# Circlez8a_v2.net
KiCad netlist of a schematic drawn in EAGLE
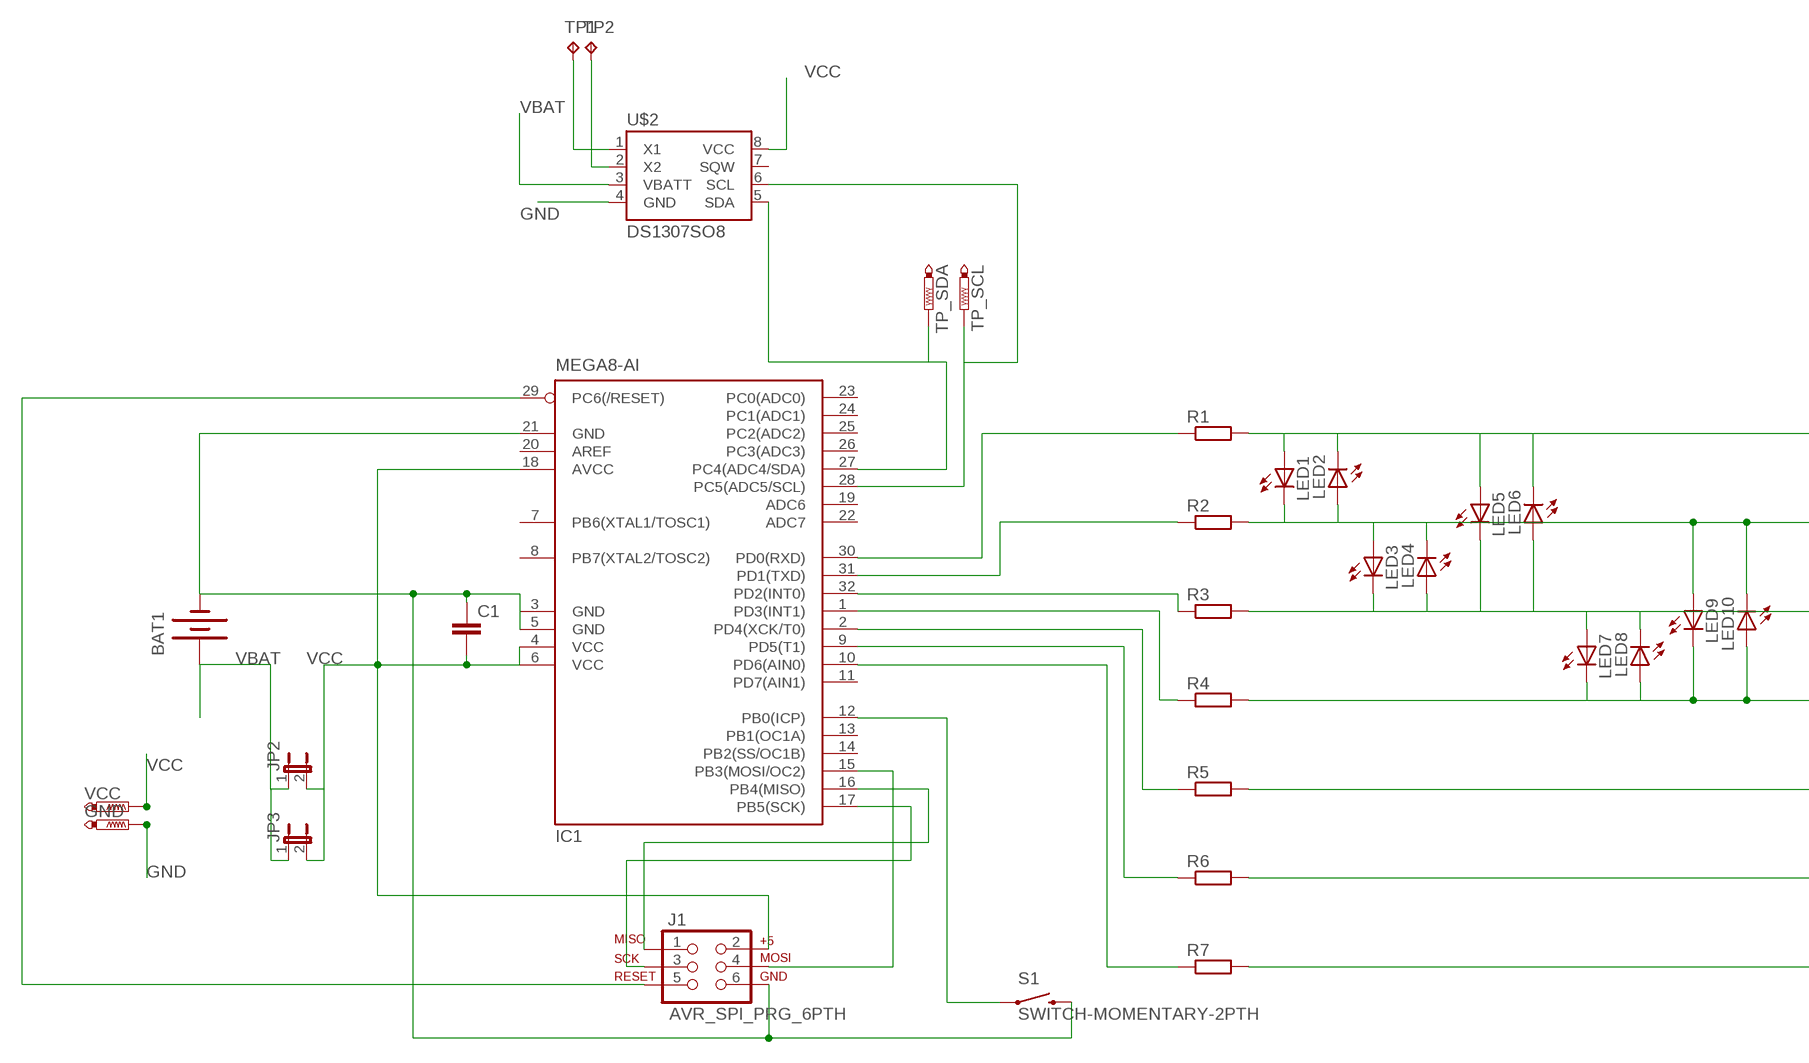
[diagram p0: schematic, sheet 1, part 1 of 2]
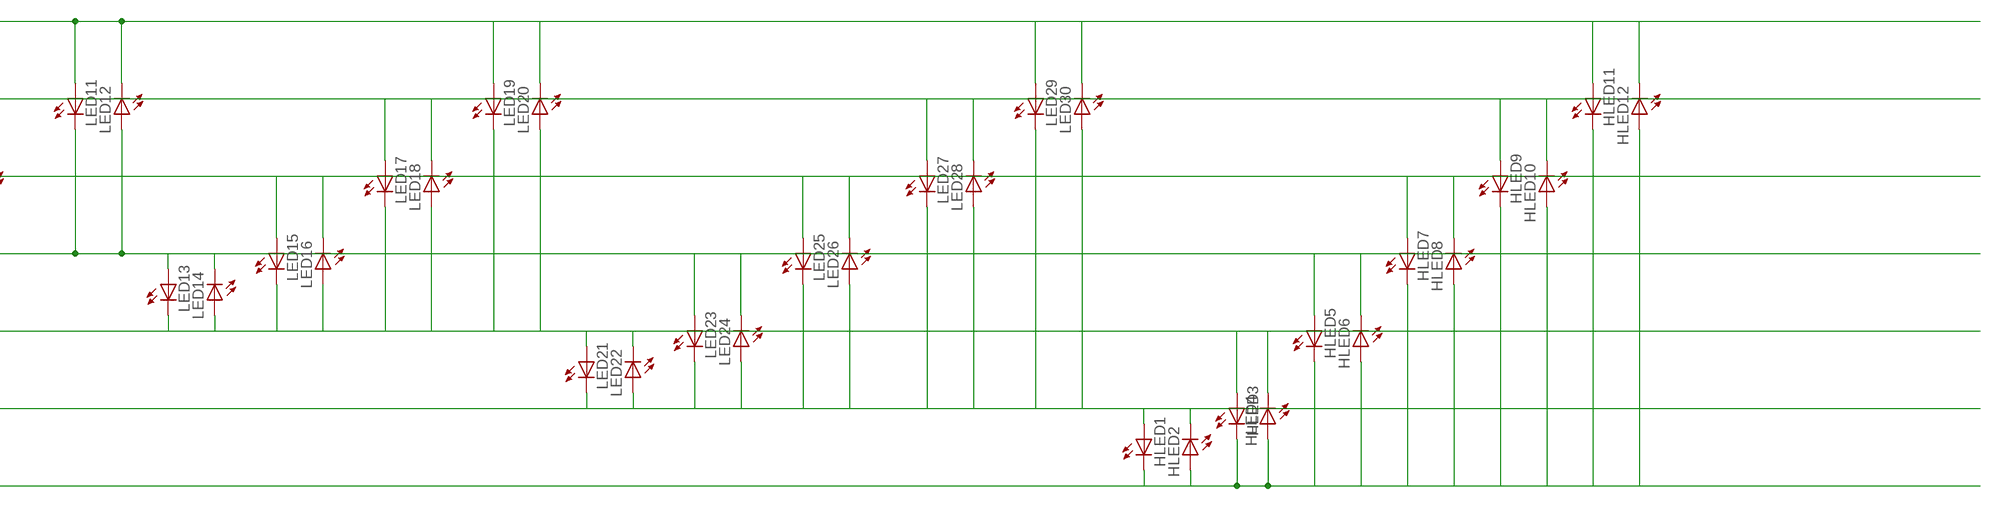
[diagram p1: schematic, sheet 1, part 2 of 2]

(export (version "E")
  (design (tool "Eeschema 10.0.6"))
  (components
    (comp (ref "BAT1")
      (value "BATTERY20PTH")
      (footprint "eagle-import:BATTCOM_20MM_PTH")
      (libsource (lib "eagle-import") (part "BATTERY20PTH"))
    )
    (comp (ref "C1")
      (value "C-EU025-024X044")
      (footprint "eagle-import:C025-024X044")
      (libsource (lib "eagle-import") (part "C-EU025-024X044"))
    )
    (comp (ref "GND")
      (value "PTR1TP15SQ")
      (footprint "eagle-import:TP15SQ")
      (libsource (lib "eagle-import") (part "PTR1TP15SQ"))
    )
    (comp (ref "HLED1")
      (value "LEDCHIP-LED0603")
      (footprint "eagle-import:CHIP-LED0603")
      (libsource (lib "eagle-import") (part "LEDCHIP-LED0603"))
    )
    (comp (ref "HLED2")
      (value "LEDCHIP-LED0603")
      (footprint "eagle-import:CHIP-LED0603")
      (libsource (lib "eagle-import") (part "LEDCHIP-LED0603"))
    )
    (comp (ref "HLED3")
      (value "LEDCHIP-LED0603")
      (footprint "eagle-import:CHIP-LED0603")
      (libsource (lib "eagle-import") (part "LEDCHIP-LED0603"))
    )
    (comp (ref "HLED4")
      (value "LEDCHIP-LED0603")
      (footprint "eagle-import:CHIP-LED0603")
      (libsource (lib "eagle-import") (part "LEDCHIP-LED0603"))
    )
    (comp (ref "HLED5")
      (value "LEDCHIP-LED0603")
      (footprint "eagle-import:CHIP-LED0603")
      (libsource (lib "eagle-import") (part "LEDCHIP-LED0603"))
    )
    (comp (ref "HLED6")
      (value "LEDCHIP-LED0603")
      (footprint "eagle-import:CHIP-LED0603")
      (libsource (lib "eagle-import") (part "LEDCHIP-LED0603"))
    )
    (comp (ref "HLED7")
      (value "LEDCHIP-LED0603")
      (footprint "eagle-import:CHIP-LED0603")
      (libsource (lib "eagle-import") (part "LEDCHIP-LED0603"))
    )
    (comp (ref "HLED8")
      (value "LEDCHIP-LED0603")
      (footprint "eagle-import:CHIP-LED0603")
      (libsource (lib "eagle-import") (part "LEDCHIP-LED0603"))
    )
    (comp (ref "HLED9")
      (value "LEDCHIP-LED0603")
      (footprint "eagle-import:CHIP-LED0603")
      (libsource (lib "eagle-import") (part "LEDCHIP-LED0603"))
    )
    (comp (ref "HLED10")
      (value "LEDCHIP-LED0603")
      (footprint "eagle-import:CHIP-LED0603")
      (libsource (lib "eagle-import") (part "LEDCHIP-LED0603"))
    )
    (comp (ref "HLED11")
      (value "LEDCHIP-LED0603")
      (footprint "eagle-import:CHIP-LED0603")
      (libsource (lib "eagle-import") (part "LEDCHIP-LED0603"))
    )
    (comp (ref "HLED12")
      (value "LEDCHIP-LED0603")
      (footprint "eagle-import:CHIP-LED0603")
      (libsource (lib "eagle-import") (part "LEDCHIP-LED0603"))
    )
    (comp (ref "IC1")
      (value "MEGA8-AI")
      (footprint "eagle-import:TQFP32-08")
      (fields (field (name "MPN") "ATMEGA8-16AU"))
      (libsource (lib "eagle-import") (part "MEGA8-AI"))
    )
    (comp (ref "J1")
      (value "AVR_SPI_PRG_6PTH")
      (footprint "eagle-import:2X3")
      (libsource (lib "eagle-import") (part "AVR_SPI_PRG_6PTH"))
    )
    (comp (ref "JP2")
      (value "JUMPER-2SMD-NO")
      (footprint "eagle-import:SJ_2S-NO")
      (libsource (lib "eagle-import") (part "JUMPER-2SMD-NO"))
    )
    (comp (ref "JP3")
      (value "JUMPER-2PTH")
      (footprint "eagle-import:1X02")
      (libsource (lib "eagle-import") (part "JUMPER-2PTH"))
    )
    (comp (ref "LED1")
      (value "LEDCHIPLED_0603")
      (footprint "eagle-import:CHIPLED_0603")
      (libsource (lib "eagle-import") (part "LEDCHIPLED_0603"))
    )
    (comp (ref "LED2")
      (value "LEDCHIPLED_0603")
      (footprint "eagle-import:CHIPLED_0603")
      (libsource (lib "eagle-import") (part "LEDCHIPLED_0603"))
    )
    (comp (ref "LED3")
      (value "LEDCHIPLED_0603")
      (footprint "eagle-import:CHIPLED_0603")
      (libsource (lib "eagle-import") (part "LEDCHIPLED_0603"))
    )
    (comp (ref "LED4")
      (value "LEDCHIPLED_0603")
      (footprint "eagle-import:CHIPLED_0603")
      (libsource (lib "eagle-import") (part "LEDCHIPLED_0603"))
    )
    (comp (ref "LED5")
      (value "LEDCHIPLED_0603")
      (footprint "eagle-import:CHIPLED_0603")
      (libsource (lib "eagle-import") (part "LEDCHIPLED_0603"))
    )
    (comp (ref "LED6")
      (value "LEDCHIPLED_0603")
      (footprint "eagle-import:CHIPLED_0603")
      (libsource (lib "eagle-import") (part "LEDCHIPLED_0603"))
    )
    (comp (ref "LED7")
      (value "LEDCHIPLED_0603")
      (footprint "eagle-import:CHIPLED_0603")
      (libsource (lib "eagle-import") (part "LEDCHIPLED_0603"))
    )
    (comp (ref "LED8")
      (value "LEDCHIPLED_0603")
      (footprint "eagle-import:CHIPLED_0603")
      (libsource (lib "eagle-import") (part "LEDCHIPLED_0603"))
    )
    (comp (ref "LED9")
      (value "LEDCHIPLED_0603")
      (footprint "eagle-import:CHIPLED_0603")
      (libsource (lib "eagle-import") (part "LEDCHIPLED_0603"))
    )
    (comp (ref "LED10")
      (value "LEDCHIPLED_0603")
      (footprint "eagle-import:CHIPLED_0603")
      (libsource (lib "eagle-import") (part "LEDCHIPLED_0603"))
    )
    (comp (ref "LED11")
      (value "LEDCHIPLED_0603")
      (footprint "eagle-import:CHIPLED_0603")
      (libsource (lib "eagle-import") (part "LEDCHIPLED_0603"))
    )
    (comp (ref "LED12")
      (value "LEDCHIPLED_0603")
      (footprint "eagle-import:CHIPLED_0603")
      (libsource (lib "eagle-import") (part "LEDCHIPLED_0603"))
    )
    (comp (ref "LED13")
      (value "LEDCHIPLED_0603")
      (footprint "eagle-import:CHIPLED_0603")
      (libsource (lib "eagle-import") (part "LEDCHIPLED_0603"))
    )
    (comp (ref "LED14")
      (value "LEDCHIPLED_0603")
      (footprint "eagle-import:CHIPLED_0603")
      (libsource (lib "eagle-import") (part "LEDCHIPLED_0603"))
    )
    (comp (ref "LED15")
      (value "LEDCHIPLED_0603")
      (footprint "eagle-import:CHIPLED_0603")
      (libsource (lib "eagle-import") (part "LEDCHIPLED_0603"))
    )
    (comp (ref "LED16")
      (value "LEDCHIPLED_0603")
      (footprint "eagle-import:CHIPLED_0603")
      (libsource (lib "eagle-import") (part "LEDCHIPLED_0603"))
    )
    (comp (ref "LED17")
      (value "LEDCHIPLED_0603")
      (footprint "eagle-import:CHIPLED_0603")
      (libsource (lib "eagle-import") (part "LEDCHIPLED_0603"))
    )
    (comp (ref "LED18")
      (value "LEDCHIPLED_0603")
      (footprint "eagle-import:CHIPLED_0603")
      (libsource (lib "eagle-import") (part "LEDCHIPLED_0603"))
    )
    (comp (ref "LED19")
      (value "LEDCHIPLED_0603")
      (footprint "eagle-import:CHIPLED_0603")
      (libsource (lib "eagle-import") (part "LEDCHIPLED_0603"))
    )
    (comp (ref "LED20")
      (value "LEDCHIPLED_0603")
      (footprint "eagle-import:CHIPLED_0603")
      (libsource (lib "eagle-import") (part "LEDCHIPLED_0603"))
    )
    (comp (ref "LED21")
      (value "LEDCHIPLED_0603")
      (footprint "eagle-import:CHIPLED_0603")
      (libsource (lib "eagle-import") (part "LEDCHIPLED_0603"))
    )
    (comp (ref "LED22")
      (value "LEDCHIPLED_0603")
      (footprint "eagle-import:CHIPLED_0603")
      (libsource (lib "eagle-import") (part "LEDCHIPLED_0603"))
    )
    (comp (ref "LED23")
      (value "LEDCHIPLED_0603")
      (footprint "eagle-import:CHIPLED_0603")
      (libsource (lib "eagle-import") (part "LEDCHIPLED_0603"))
    )
    (comp (ref "LED24")
      (value "LEDCHIPLED_0603")
      (footprint "eagle-import:CHIPLED_0603")
      (libsource (lib "eagle-import") (part "LEDCHIPLED_0603"))
    )
    (comp (ref "LED25")
      (value "LEDCHIPLED_0603")
      (footprint "eagle-import:CHIPLED_0603")
      (libsource (lib "eagle-import") (part "LEDCHIPLED_0603"))
    )
    (comp (ref "LED26")
      (value "LEDCHIPLED_0603")
      (footprint "eagle-import:CHIPLED_0603")
      (libsource (lib "eagle-import") (part "LEDCHIPLED_0603"))
    )
    (comp (ref "LED27")
      (value "LEDCHIPLED_0603")
      (footprint "eagle-import:CHIPLED_0603")
      (libsource (lib "eagle-import") (part "LEDCHIPLED_0603"))
    )
    (comp (ref "LED28")
      (value "LEDCHIPLED_0603")
      (footprint "eagle-import:CHIPLED_0603")
      (libsource (lib "eagle-import") (part "LEDCHIPLED_0603"))
    )
    (comp (ref "LED29")
      (value "LEDCHIPLED_0603")
      (footprint "eagle-import:CHIPLED_0603")
      (libsource (lib "eagle-import") (part "LEDCHIPLED_0603"))
    )
    (comp (ref "LED30")
      (value "LEDCHIPLED_0603")
      (footprint "eagle-import:CHIPLED_0603")
      (libsource (lib "eagle-import") (part "LEDCHIPLED_0603"))
    )
    (comp (ref "R1")
      (value "R-EU_R1206")
      (footprint "eagle-import:R1206")
      (libsource (lib "eagle-import") (part "R-EU_R1206"))
    )
    (comp (ref "R2")
      (value "R-EU_R1206")
      (footprint "eagle-import:R1206")
      (libsource (lib "eagle-import") (part "R-EU_R1206"))
    )
    (comp (ref "R3")
      (value "R-EU_R1206")
      (footprint "eagle-import:R1206")
      (libsource (lib "eagle-import") (part "R-EU_R1206"))
    )
    (comp (ref "R4")
      (value "R-EU_R1206")
      (footprint "eagle-import:R1206")
      (libsource (lib "eagle-import") (part "R-EU_R1206"))
    )
    (comp (ref "R5")
      (value "R-EU_R1206")
      (footprint "eagle-import:R1206")
      (libsource (lib "eagle-import") (part "R-EU_R1206"))
    )
    (comp (ref "R6")
      (value "R-EU_R1206")
      (footprint "eagle-import:R1206")
      (libsource (lib "eagle-import") (part "R-EU_R1206"))
    )
    (comp (ref "R7")
      (value "R-EU_R1206")
      (footprint "eagle-import:R1206")
      (libsource (lib "eagle-import") (part "R-EU_R1206"))
    )
    (comp (ref "S1")
      (value "SWITCH-MOMENTARY-2PTH")
      (footprint "eagle-import:TACTILE-PTH")
      (libsource (lib "eagle-import") (part "SWITCH-MOMENTARY-2PTH"))
    )
    (comp (ref "TP1")
      (value "TPTP13SQ")
      (footprint "eagle-import:TP13SQ")
      (libsource (lib "eagle-import") (part "TPTP13SQ"))
    )
    (comp (ref "TP2")
      (value "TPTP13SQ")
      (footprint "eagle-import:TP13SQ")
      (libsource (lib "eagle-import") (part "TPTP13SQ"))
    )
    (comp (ref "TP_SCL")
      (value "PTR1TP09SQ")
      (footprint "eagle-import:TP09SQ")
      (libsource (lib "eagle-import") (part "PTR1TP09SQ"))
    )
    (comp (ref "TP_SDA")
      (value "PTR1TP09SQ")
      (footprint "eagle-import:TP09SQ")
      (libsource (lib "eagle-import") (part "PTR1TP09SQ"))
    )
    (comp (ref "U$2")
      (value "DS1307SO8")
      (footprint "eagle-import:SO08")
      (libsource (lib "eagle-import") (part "DS1307SO8"))
    )
    (comp (ref "VCC")
      (value "PTR1TP15SQ")
      (footprint "eagle-import:TP15SQ")
      (libsource (lib "eagle-import") (part "PTR1TP15SQ"))
    )
  )
  (nets
    (net (code "1") (name "/GND") (class "Default")
      (node (ref "BAT1") (pin "2") (pinfunction "-_2") (pintype "power_in"))
      (node (ref "C1") (pin "1") (pinfunction "1_1") (pintype "passive"))
      (node (ref "GND") (pin "TP") (pinfunction "TP_TP") (pintype "input"))
      (node (ref "IC1") (pin "21") (pinfunction "GND_21") (pintype "power_in"))
      (node (ref "IC1") (pin "3") (pinfunction "GND_3") (pintype "power_in"))
      (node (ref "IC1") (pin "5") (pinfunction "GND_5") (pintype "power_in"))
      (node (ref "J1") (pin "6") (pinfunction "6_6") (pintype "passive"))
      (node (ref "S1") (pin "3") (pinfunction "2_3") (pintype "passive"))
      (node (ref "U$2") (pin "4") (pinfunction "GND_4") (pintype "bidirectional"))
    )
    (net (code "2") (name "/VBAT") (class "Default")
      (node (ref "BAT1") (pin "1") (pinfunction "+_1") (pintype "power_in"))
      (node (ref "JP2") (pin "1") (pinfunction "1_1") (pintype "passive"))
      (node (ref "JP3") (pin "1") (pinfunction "1_1") (pintype "passive"))
      (node (ref "U$2") (pin "3") (pinfunction "VBATT_3") (pintype "bidirectional"))
    )
    (net (code "3") (name "/VCC") (class "Default")
      (node (ref "C1") (pin "2") (pinfunction "2_2") (pintype "passive"))
      (node (ref "IC1") (pin "18") (pinfunction "AVCC_18") (pintype "power_in"))
      (node (ref "IC1") (pin "4") (pinfunction "VCC_4") (pintype "power_in"))
      (node (ref "IC1") (pin "6") (pinfunction "VCC_6") (pintype "power_in"))
      (node (ref "J1") (pin "2") (pinfunction "2_2") (pintype "passive"))
      (node (ref "JP2") (pin "2") (pinfunction "2_2") (pintype "passive"))
      (node (ref "JP3") (pin "2") (pinfunction "2_2") (pintype "passive"))
      (node (ref "U$2") (pin "8") (pinfunction "VCC_8") (pintype "bidirectional"))
      (node (ref "VCC") (pin "TP") (pinfunction "TP_TP") (pintype "input"))
    )
    (net (code "4") (name "Net-(HLED1-PadA)") (class "Default")
      (node (ref "HLED1") (pin "A") (pinfunction "A_A") (pintype "passive"))
      (node (ref "HLED2") (pin "C") (pinfunction "C_C") (pintype "passive"))
      (node (ref "LED21") (pin "C") (pinfunction "C_C") (pintype "passive"))
      (node (ref "LED22") (pin "A") (pinfunction "A_A") (pintype "passive"))
      (node (ref "LED23") (pin "C") (pinfunction "C_C") (pintype "passive"))
      (node (ref "LED24") (pin "A") (pinfunction "A_A") (pintype "passive"))
      (node (ref "LED25") (pin "C") (pinfunction "C_C") (pintype "passive"))
      (node (ref "LED26") (pin "A") (pinfunction "A_A") (pintype "passive"))
      (node (ref "LED27") (pin "C") (pinfunction "C_C") (pintype "passive"))
      (node (ref "LED28") (pin "A") (pinfunction "A_A") (pintype "passive"))
      (node (ref "LED29") (pin "C") (pinfunction "C_C") (pintype "passive"))
      (node (ref "LED30") (pin "A") (pinfunction "A_A") (pintype "passive"))
      (node (ref "R6") (pin "2") (pinfunction "2_2") (pintype "passive"))
    )
    (net (code "5") (name "Net-(HLED1-PadC)") (class "Default")
      (node (ref "HLED1") (pin "C") (pinfunction "C_C") (pintype "passive"))
      (node (ref "HLED10") (pin "A") (pinfunction "A_A") (pintype "passive"))
      (node (ref "HLED11") (pin "C") (pinfunction "C_C") (pintype "passive"))
      (node (ref "HLED12") (pin "A") (pinfunction "A_A") (pintype "passive"))
      (node (ref "HLED2") (pin "A") (pinfunction "A_A") (pintype "passive"))
      (node (ref "HLED3") (pin "C") (pinfunction "C_C") (pintype "passive"))
      (node (ref "HLED4") (pin "A") (pinfunction "A_A") (pintype "passive"))
      (node (ref "HLED5") (pin "C") (pinfunction "C_C") (pintype "passive"))
      (node (ref "HLED6") (pin "A") (pinfunction "A_A") (pintype "passive"))
      (node (ref "HLED7") (pin "C") (pinfunction "C_C") (pintype "passive"))
      (node (ref "HLED8") (pin "A") (pinfunction "A_A") (pintype "passive"))
      (node (ref "HLED9") (pin "C") (pinfunction "C_C") (pintype "passive"))
      (node (ref "R7") (pin "2") (pinfunction "2_2") (pintype "passive"))
    )
    (net (code "6") (name "Net-(HLED3-PadA)") (class "Default")
      (node (ref "HLED3") (pin "A") (pinfunction "A_A") (pintype "passive"))
      (node (ref "HLED4") (pin "C") (pinfunction "C_C") (pintype "passive"))
      (node (ref "LED13") (pin "C") (pinfunction "C_C") (pintype "passive"))
      (node (ref "LED14") (pin "A") (pinfunction "A_A") (pintype "passive"))
      (node (ref "LED15") (pin "C") (pinfunction "C_C") (pintype "passive"))
      (node (ref "LED16") (pin "A") (pinfunction "A_A") (pintype "passive"))
      (node (ref "LED17") (pin "C") (pinfunction "C_C") (pintype "passive"))
      (node (ref "LED18") (pin "A") (pinfunction "A_A") (pintype "passive"))
      (node (ref "LED19") (pin "C") (pinfunction "C_C") (pintype "passive"))
      (node (ref "LED20") (pin "A") (pinfunction "A_A") (pintype "passive"))
      (node (ref "LED21") (pin "A") (pinfunction "A_A") (pintype "passive"))
      (node (ref "LED22") (pin "C") (pinfunction "C_C") (pintype "passive"))
      (node (ref "R5") (pin "2") (pinfunction "2_2") (pintype "passive"))
    )
    (net (code "7") (name "Net-(HLED5-PadA)") (class "Default")
      (node (ref "HLED5") (pin "A") (pinfunction "A_A") (pintype "passive"))
      (node (ref "HLED6") (pin "C") (pinfunction "C_C") (pintype "passive"))
      (node (ref "LED10") (pin "A") (pinfunction "A_A") (pintype "passive"))
      (node (ref "LED11") (pin "C") (pinfunction "C_C") (pintype "passive"))
      (node (ref "LED12") (pin "A") (pinfunction "A_A") (pintype "passive"))
      (node (ref "LED13") (pin "A") (pinfunction "A_A") (pintype "passive"))
      (node (ref "LED14") (pin "C") (pinfunction "C_C") (pintype "passive"))
      (node (ref "LED23") (pin "A") (pinfunction "A_A") (pintype "passive"))
      (node (ref "LED24") (pin "C") (pinfunction "C_C") (pintype "passive"))
      (node (ref "LED7") (pin "C") (pinfunction "C_C") (pintype "passive"))
      (node (ref "LED8") (pin "A") (pinfunction "A_A") (pintype "passive"))
      (node (ref "LED9") (pin "C") (pinfunction "C_C") (pintype "passive"))
      (node (ref "R4") (pin "2") (pinfunction "2_2") (pintype "passive"))
    )
    (net (code "8") (name "Net-(HLED7-PadA)") (class "Default")
      (node (ref "HLED7") (pin "A") (pinfunction "A_A") (pintype "passive"))
      (node (ref "HLED8") (pin "C") (pinfunction "C_C") (pintype "passive"))
      (node (ref "LED15") (pin "A") (pinfunction "A_A") (pintype "passive"))
      (node (ref "LED16") (pin "C") (pinfunction "C_C") (pintype "passive"))
      (node (ref "LED25") (pin "A") (pinfunction "A_A") (pintype "passive"))
      (node (ref "LED26") (pin "C") (pinfunction "C_C") (pintype "passive"))
      (node (ref "LED3") (pin "C") (pinfunction "C_C") (pintype "passive"))
      (node (ref "LED4") (pin "A") (pinfunction "A_A") (pintype "passive"))
      (node (ref "LED5") (pin "C") (pinfunction "C_C") (pintype "passive"))
      (node (ref "LED6") (pin "A") (pinfunction "A_A") (pintype "passive"))
      (node (ref "LED7") (pin "A") (pinfunction "A_A") (pintype "passive"))
      (node (ref "LED8") (pin "C") (pinfunction "C_C") (pintype "passive"))
      (node (ref "R3") (pin "2") (pinfunction "2_2") (pintype "passive"))
    )
    (net (code "9") (name "Net-(HLED10-PadC)") (class "Default")
      (node (ref "HLED10") (pin "C") (pinfunction "C_C") (pintype "passive"))
      (node (ref "HLED9") (pin "A") (pinfunction "A_A") (pintype "passive"))
      (node (ref "LED1") (pin "C") (pinfunction "C_C") (pintype "passive"))
      (node (ref "LED10") (pin "C") (pinfunction "C_C") (pintype "passive"))
      (node (ref "LED17") (pin "A") (pinfunction "A_A") (pintype "passive"))
      (node (ref "LED18") (pin "C") (pinfunction "C_C") (pintype "passive"))
      (node (ref "LED2") (pin "A") (pinfunction "A_A") (pintype "passive"))
      (node (ref "LED27") (pin "A") (pinfunction "A_A") (pintype "passive"))
      (node (ref "LED28") (pin "C") (pinfunction "C_C") (pintype "passive"))
      (node (ref "LED3") (pin "A") (pinfunction "A_A") (pintype "passive"))
      (node (ref "LED4") (pin "C") (pinfunction "C_C") (pintype "passive"))
      (node (ref "LED9") (pin "A") (pinfunction "A_A") (pintype "passive"))
      (node (ref "R2") (pin "2") (pinfunction "2_2") (pintype "passive"))
    )
    (net (code "10") (name "Net-(HLED11-PadA)") (class "Default")
      (node (ref "HLED11") (pin "A") (pinfunction "A_A") (pintype "passive"))
      (node (ref "HLED12") (pin "C") (pinfunction "C_C") (pintype "passive"))
      (node (ref "LED1") (pin "A") (pinfunction "A_A") (pintype "passive"))
      (node (ref "LED11") (pin "A") (pinfunction "A_A") (pintype "passive"))
      (node (ref "LED12") (pin "C") (pinfunction "C_C") (pintype "passive"))
      (node (ref "LED19") (pin "A") (pinfunction "A_A") (pintype "passive"))
      (node (ref "LED2") (pin "C") (pinfunction "C_C") (pintype "passive"))
      (node (ref "LED20") (pin "C") (pinfunction "C_C") (pintype "passive"))
      (node (ref "LED29") (pin "A") (pinfunction "A_A") (pintype "passive"))
      (node (ref "LED30") (pin "C") (pinfunction "C_C") (pintype "passive"))
      (node (ref "LED5") (pin "A") (pinfunction "A_A") (pintype "passive"))
      (node (ref "LED6") (pin "C") (pinfunction "C_C") (pintype "passive"))
      (node (ref "R1") (pin "2") (pinfunction "2_2") (pintype "passive"))
    )
    (net (code "11") (name "Net-(IC1-PB0(ICP))") (class "Default")
      (node (ref "IC1") (pin "12") (pinfunction "PB0(ICP)_12") (pintype "bidirectional"))
      (node (ref "S1") (pin "1") (pinfunction "1_1") (pintype "passive"))
    )
    (net (code "12") (name "Net-(IC1-PB3(MOSI{slash}OC2))") (class "Default")
      (node (ref "IC1") (pin "15") (pinfunction "PB3(MOSI/OC2)_15") (pintype "bidirectional"))
      (node (ref "J1") (pin "4") (pinfunction "4_4") (pintype "passive"))
    )
    (net (code "13") (name "Net-(IC1-PB4(MISO))") (class "Default")
      (node (ref "IC1") (pin "16") (pinfunction "PB4(MISO)_16") (pintype "bidirectional"))
      (node (ref "J1") (pin "1") (pinfunction "1_1") (pintype "passive"))
    )
    (net (code "14") (name "Net-(IC1-PB5(SCK))") (class "Default")
      (node (ref "IC1") (pin "17") (pinfunction "PB5(SCK)_17") (pintype "bidirectional"))
      (node (ref "J1") (pin "3") (pinfunction "3_3") (pintype "passive"))
    )
    (net (code "15") (name "Net-(IC1-PC4(ADC4{slash}SDA))") (class "Default")
      (node (ref "IC1") (pin "27") (pinfunction "PC4(ADC4/SDA)_27") (pintype "bidirectional"))
      (node (ref "TP_SDA") (pin "TP") (pinfunction "TP_TP") (pintype "input"))
      (node (ref "U$2") (pin "5") (pinfunction "SDA_5") (pintype "bidirectional"))
    )
    (net (code "16") (name "Net-(IC1-PC5(ADC5{slash}SCL))") (class "Default")
      (node (ref "IC1") (pin "28") (pinfunction "PC5(ADC5/SCL)_28") (pintype "bidirectional"))
      (node (ref "TP_SCL") (pin "TP") (pinfunction "TP_TP") (pintype "input"))
      (node (ref "U$2") (pin "6") (pinfunction "SCL_6") (pintype "bidirectional"))
    )
    (net (code "17") (name "Net-(IC1-PC6({slash}RESET))") (class "Default")
      (node (ref "IC1") (pin "29") (pinfunction "PC6(/RESET)_29") (pintype "bidirectional"))
      (node (ref "J1") (pin "5") (pinfunction "5_5") (pintype "passive"))
    )
    (net (code "18") (name "Net-(IC1-PD0(RXD))") (class "Default")
      (node (ref "IC1") (pin "30") (pinfunction "PD0(RXD)_30") (pintype "bidirectional"))
      (node (ref "R1") (pin "1") (pinfunction "1_1") (pintype "passive"))
    )
    (net (code "19") (name "Net-(IC1-PD1(TXD))") (class "Default")
      (node (ref "IC1") (pin "31") (pinfunction "PD1(TXD)_31") (pintype "bidirectional"))
      (node (ref "R2") (pin "1") (pinfunction "1_1") (pintype "passive"))
    )
    (net (code "20") (name "Net-(IC1-PD2(INT0))") (class "Default")
      (node (ref "IC1") (pin "32") (pinfunction "PD2(INT0)_32") (pintype "bidirectional"))
      (node (ref "R3") (pin "1") (pinfunction "1_1") (pintype "passive"))
    )
    (net (code "21") (name "Net-(IC1-PD3(INT1))") (class "Default")
      (node (ref "IC1") (pin "1") (pinfunction "PD3(INT1)_1") (pintype "bidirectional"))
      (node (ref "R4") (pin "1") (pinfunction "1_1") (pintype "passive"))
    )
    (net (code "22") (name "Net-(IC1-PD4(XCK{slash}T0))") (class "Default")
      (node (ref "IC1") (pin "2") (pinfunction "PD4(XCK/T0)_2") (pintype "bidirectional"))
      (node (ref "R5") (pin "1") (pinfunction "1_1") (pintype "passive"))
    )
    (net (code "23") (name "Net-(IC1-PD5(T1))") (class "Default")
      (node (ref "IC1") (pin "9") (pinfunction "PD5(T1)_9") (pintype "bidirectional"))
      (node (ref "R6") (pin "1") (pinfunction "1_1") (pintype "passive"))
    )
    (net (code "24") (name "Net-(IC1-PD6(AIN0))") (class "Default")
      (node (ref "IC1") (pin "10") (pinfunction "PD6(AIN0)_10") (pintype "bidirectional"))
      (node (ref "R7") (pin "1") (pinfunction "1_1") (pintype "passive"))
    )
    (net (code "25") (name "Net-(U$2-X1)") (class "Default")
      (node (ref "TP1") (pin "TP") (pinfunction "TP_TP") (pintype "input"))
      (node (ref "U$2") (pin "1") (pinfunction "X1_1") (pintype "bidirectional"))
    )
    (net (code "26") (name "Net-(U$2-X2)") (class "Default")
      (node (ref "TP2") (pin "TP") (pinfunction "TP_TP") (pintype "input"))
      (node (ref "U$2") (pin "2") (pinfunction "X2_2") (pintype "bidirectional"))
    )
    (net (code "27") (name "unconnected-(IC1-ADC6-Pad19)") (class "Default")
      (node (ref "IC1") (pin "19") (pinfunction "ADC6_19") (pintype "bidirectional"))
    )
    (net (code "28") (name "unconnected-(IC1-ADC7-Pad22)") (class "Default")
      (node (ref "IC1") (pin "22") (pinfunction "ADC7_22") (pintype "bidirectional"))
    )
    (net (code "29") (name "unconnected-(IC1-AREF-Pad20)") (class "Default")
      (node (ref "IC1") (pin "20") (pinfunction "AREF_20") (pintype "passive"))
    )
    (net (code "30") (name "unconnected-(IC1-PB1(OC1A)-Pad13)") (class "Default")
      (node (ref "IC1") (pin "13") (pinfunction "PB1(OC1A)_13") (pintype "bidirectional"))
    )
    (net (code "31") (name "unconnected-(IC1-PB2(SS{slash}OC1B)-Pad14)") (class "Default")
      (node (ref "IC1") (pin "14") (pinfunction "PB2(SS/OC1B)_14") (pintype "bidirectional"))
    )
    (net (code "32") (name "unconnected-(IC1-PB6(XTAL1{slash}TOSC1)-Pad7)") (class "Default")
      (node (ref "IC1") (pin "7") (pinfunction "PB6(XTAL1/TOSC1)_7") (pintype "bidirectional"))
    )
    (net (code "33") (name "unconnected-(IC1-PB7(XTAL2{slash}TOSC2)-Pad8)") (class "Default")
      (node (ref "IC1") (pin "8") (pinfunction "PB7(XTAL2/TOSC2)_8") (pintype "bidirectional"))
    )
    (net (code "34") (name "unconnected-(IC1-PC0(ADC0)-Pad23)") (class "Default")
      (node (ref "IC1") (pin "23") (pinfunction "PC0(ADC0)_23") (pintype "bidirectional"))
    )
    (net (code "35") (name "unconnected-(IC1-PC1(ADC1)-Pad24)") (class "Default")
      (node (ref "IC1") (pin "24") (pinfunction "PC1(ADC1)_24") (pintype "bidirectional"))
    )
    (net (code "36") (name "unconnected-(IC1-PC2(ADC2)-Pad25)") (class "Default")
      (node (ref "IC1") (pin "25") (pinfunction "PC2(ADC2)_25") (pintype "bidirectional"))
    )
    (net (code "37") (name "unconnected-(IC1-PC3(ADC3)-Pad26)") (class "Default")
      (node (ref "IC1") (pin "26") (pinfunction "PC3(ADC3)_26") (pintype "bidirectional"))
    )
    (net (code "38") (name "unconnected-(IC1-PD7(AIN1)-Pad11)") (class "Default")
      (node (ref "IC1") (pin "11") (pinfunction "PD7(AIN1)_11") (pintype "bidirectional"))
    )
    (net (code "39") (name "unconnected-(U$2-SQW-Pad7)") (class "Default")
      (node (ref "U$2") (pin "7") (pinfunction "SQW_7") (pintype "bidirectional"))
    )
  )
)
